# tulip_breakout.net
KiCad netlist of a schematic drawn in EAGLE
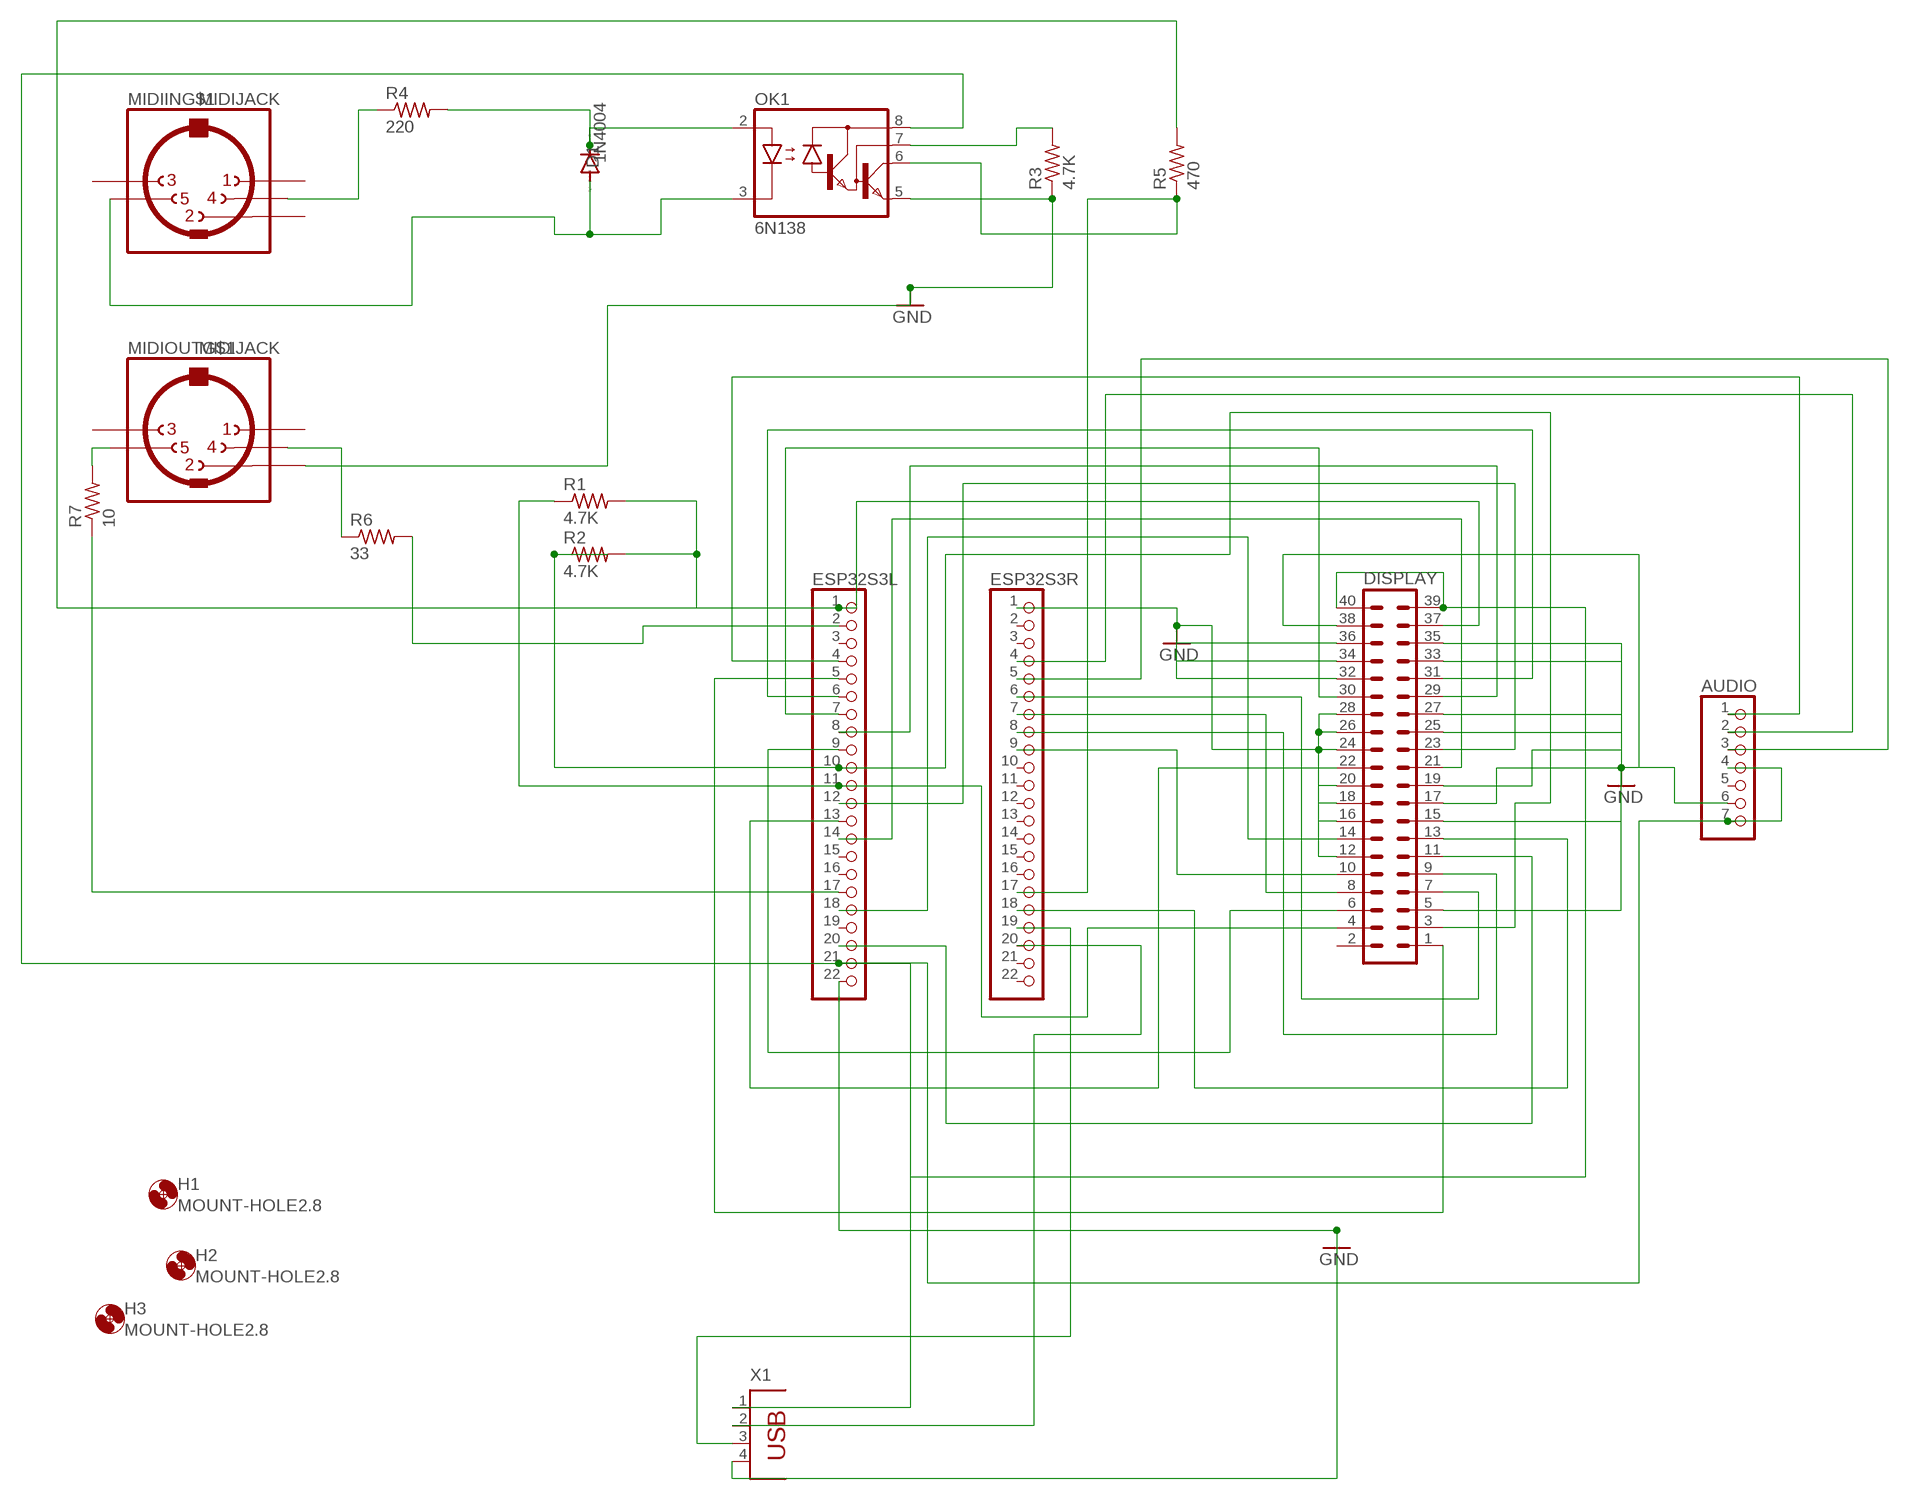
[diagram p0: schematic, sheet 1]

(export (version "E")
  (design (tool "Eeschema 10.0.6"))
  (components
    (comp (ref "AUDIO")
      (value "PINHD-1X7")
      (footprint "eagle-import:1X07")
      (libsource (lib "eagle-import") (part "PINHD-1X7"))
    )
    (comp (ref "D1")
      (value "1N4004")
      (footprint "eagle-import:DO41-10")
      (libsource (lib "eagle-import") (part "1N4004"))
    )
    (comp (ref "DISPLAY")
      (value "MA20-2")
      (footprint "eagle-import:MA20-2")
      (libsource (lib "eagle-import") (part "MA20-2"))
    )
    (comp (ref "ESP32S3L")
      (value "PINHD-1X22")
      (footprint "eagle-import:1X22")
      (libsource (lib "eagle-import") (part "PINHD-1X22"))
    )
    (comp (ref "ESP32S3R")
      (value "PINHD-1X22")
      (footprint "eagle-import:1X22")
      (libsource (lib "eagle-import") (part "PINHD-1X22"))
    )
    (comp (ref "H1")
      (value "MOUNT-HOLE2.8")
      (footprint "eagle-import:2,8")
      (libsource (lib "eagle-import") (part "MOUNT-HOLE2.8"))
    )
    (comp (ref "H2")
      (value "MOUNT-HOLE2.8")
      (footprint "eagle-import:2,8")
      (libsource (lib "eagle-import") (part "MOUNT-HOLE2.8"))
    )
    (comp (ref "H3")
      (value "MOUNT-HOLE2.8")
      (footprint "eagle-import:2,8")
      (libsource (lib "eagle-import") (part "MOUNT-HOLE2.8"))
    )
    (comp (ref "MIDIIN")
      (value "MIDIJACK")
      (footprint "eagle-import:CP-2350")
      (libsource (lib "eagle-import") (part "MIDIJACK"))
    )
    (comp (ref "MIDIOUT")
      (value "MIDIJACK")
      (footprint "eagle-import:CP-2350")
      (libsource (lib "eagle-import") (part "MIDIJACK"))
    )
    (comp (ref "OK1")
      (value "6N138")
      (footprint "eagle-import:DIL08")
      (fields (field (name "MF") "VISHAY/TELEFUNKEN"))
      (libsource (lib "eagle-import") (part "6N138"))
    )
    (comp (ref "R1")
      (value "4.7K")
      (footprint "eagle-import:0204_7")
      (libsource (lib "eagle-import") (part "R-US_0204/7"))
    )
    (comp (ref "R2")
      (value "4.7K")
      (footprint "eagle-import:0204_7")
      (libsource (lib "eagle-import") (part "R-US_0204/7"))
    )
    (comp (ref "R3")
      (value "4.7K")
      (footprint "eagle-import:0204_7")
      (libsource (lib "eagle-import") (part "R-US_0204/7"))
    )
    (comp (ref "R4")
      (value "220")
      (footprint "eagle-import:0204_7")
      (libsource (lib "eagle-import") (part "R-US_0204/7"))
    )
    (comp (ref "R5")
      (value "470")
      (footprint "eagle-import:0204_7")
      (libsource (lib "eagle-import") (part "R-US_0204/7"))
    )
    (comp (ref "R6")
      (value "33")
      (footprint "eagle-import:0204_7")
      (libsource (lib "eagle-import") (part "R-US_0204/7"))
    )
    (comp (ref "R7")
      (value "10")
      (footprint "eagle-import:0204_7")
      (libsource (lib "eagle-import") (part "R-US_0204/7"))
    )
    (comp (ref "X1")
      (value "PN87520")
      (footprint "eagle-import:PN87520")
      (libsource (lib "eagle-import") (part "PN87520"))
    )
  )
  (nets
    (net (code "1") (name "GND") (class "Default")
      (node (ref "AUDIO") (pin "6") (pinfunction "6_6") (pintype "passive"))
      (node (ref "DISPLAY") (pin "12") (pinfunction "12_12") (pintype "passive"))
      (node (ref "DISPLAY") (pin "15") (pinfunction "15_15") (pintype "passive"))
      (node (ref "DISPLAY") (pin "16") (pinfunction "16_16") (pintype "passive"))
      (node (ref "DISPLAY") (pin "17") (pinfunction "17_17") (pintype "passive"))
      (node (ref "DISPLAY") (pin "18") (pinfunction "18_18") (pintype "passive"))
      (node (ref "DISPLAY") (pin "19") (pinfunction "19_19") (pintype "passive"))
      (node (ref "DISPLAY") (pin "20") (pinfunction "20_20") (pintype "passive"))
      (node (ref "DISPLAY") (pin "24") (pinfunction "24_24") (pintype "passive"))
      (node (ref "DISPLAY") (pin "25") (pinfunction "25_25") (pintype "passive"))
      (node (ref "DISPLAY") (pin "26") (pinfunction "26_26") (pintype "passive"))
      (node (ref "DISPLAY") (pin "27") (pinfunction "27_27") (pintype "passive"))
      (node (ref "DISPLAY") (pin "28") (pinfunction "28_28") (pintype "passive"))
      (node (ref "DISPLAY") (pin "32") (pinfunction "32_32") (pintype "passive"))
      (node (ref "DISPLAY") (pin "33") (pinfunction "33_33") (pintype "passive"))
      (node (ref "DISPLAY") (pin "34") (pinfunction "34_34") (pintype "passive"))
      (node (ref "DISPLAY") (pin "35") (pinfunction "35_35") (pintype "passive"))
      (node (ref "DISPLAY") (pin "36") (pinfunction "36_36") (pintype "passive"))
      (node (ref "DISPLAY") (pin "38") (pinfunction "38_38") (pintype "passive"))
      (node (ref "DISPLAY") (pin "5") (pinfunction "5_5") (pintype "passive"))
      (node (ref "ESP32S3L") (pin "22") (pinfunction "22_22") (pintype "passive"))
      (node (ref "ESP32S3R") (pin "1") (pinfunction "1_1") (pintype "passive"))
      (node (ref "MIDIOUT") (pin "2") (pinfunction "2_2") (pintype "passive"))
      (node (ref "OK1") (pin "5") (pinfunction "GND_5") (pintype "passive"))
      (node (ref "R3") (pin "1") (pinfunction "1_1") (pintype "passive"))
      (node (ref "X1") (pin "4") (pinfunction "4_4") (pintype "passive"))
    )
    (net (code "2") (name "Net-(AUDIO-Pad1)") (class "Default")
      (node (ref "AUDIO") (pin "1") (pinfunction "1_1") (pintype "passive"))
      (node (ref "ESP32S3L") (pin "4") (pinfunction "4_4") (pintype "passive"))
    )
    (net (code "3") (name "Net-(AUDIO-Pad2)") (class "Default")
      (node (ref "AUDIO") (pin "2") (pinfunction "2_2") (pintype "passive"))
      (node (ref "ESP32S3R") (pin "4") (pinfunction "4_4") (pintype "passive"))
    )
    (net (code "4") (name "Net-(AUDIO-Pad3)") (class "Default")
      (node (ref "AUDIO") (pin "3") (pinfunction "3_3") (pintype "passive"))
      (node (ref "ESP32S3R") (pin "5") (pinfunction "5_5") (pintype "passive"))
    )
    (net (code "5") (name "Net-(DISPLAY-Pad1)") (class "Default")
      (node (ref "DISPLAY") (pin "1") (pinfunction "1_1") (pintype "passive"))
      (node (ref "ESP32S3L") (pin "5") (pinfunction "5_5") (pintype "passive"))
    )
    (net (code "6") (name "Net-(DISPLAY-Pad3)") (class "Default")
      (node (ref "DISPLAY") (pin "3") (pinfunction "3_3") (pintype "passive"))
      (node (ref "ESP32S3L") (pin "10") (pinfunction "10_10") (pintype "passive"))
      (node (ref "R2") (pin "1") (pinfunction "1_1") (pintype "passive"))
    )
    (net (code "7") (name "Net-(DISPLAY-Pad4)") (class "Default")
      (node (ref "DISPLAY") (pin "4") (pinfunction "4_4") (pintype "passive"))
      (node (ref "ESP32S3L") (pin "11") (pinfunction "11_11") (pintype "passive"))
      (node (ref "R1") (pin "1") (pinfunction "1_1") (pintype "passive"))
    )
    (net (code "8") (name "Net-(DISPLAY-Pad6)") (class "Default")
      (node (ref "DISPLAY") (pin "6") (pinfunction "6_6") (pintype "passive"))
      (node (ref "ESP32S3L") (pin "9") (pinfunction "9_9") (pintype "passive"))
    )
    (net (code "9") (name "Net-(DISPLAY-Pad7)") (class "Default")
      (node (ref "DISPLAY") (pin "7") (pinfunction "7_7") (pintype "passive"))
      (node (ref "ESP32S3R") (pin "6") (pinfunction "6_6") (pintype "passive"))
    )
    (net (code "10") (name "Net-(DISPLAY-Pad8)") (class "Default")
      (node (ref "DISPLAY") (pin "8") (pinfunction "8_8") (pintype "passive"))
      (node (ref "ESP32S3R") (pin "7") (pinfunction "7_7") (pintype "passive"))
    )
    (net (code "11") (name "Net-(DISPLAY-Pad9)") (class "Default")
      (node (ref "DISPLAY") (pin "9") (pinfunction "9_9") (pintype "passive"))
      (node (ref "ESP32S3R") (pin "8") (pinfunction "8_8") (pintype "passive"))
    )
    (net (code "12") (name "Net-(DISPLAY-Pad10)") (class "Default")
      (node (ref "DISPLAY") (pin "10") (pinfunction "10_10") (pintype "passive"))
      (node (ref "ESP32S3R") (pin "9") (pinfunction "9_9") (pintype "passive"))
    )
    (net (code "13") (name "Net-(DISPLAY-Pad11)") (class "Default")
      (node (ref "DISPLAY") (pin "11") (pinfunction "11_11") (pintype "passive"))
      (node (ref "ESP32S3L") (pin "20") (pinfunction "20_20") (pintype "passive"))
    )
    (net (code "14") (name "Net-(DISPLAY-Pad13)") (class "Default")
      (node (ref "DISPLAY") (pin "13") (pinfunction "13_13") (pintype "passive"))
      (node (ref "ESP32S3R") (pin "18") (pinfunction "18_18") (pintype "passive"))
    )
    (net (code "15") (name "Net-(DISPLAY-Pad14)") (class "Default")
      (node (ref "DISPLAY") (pin "14") (pinfunction "14_14") (pintype "passive"))
      (node (ref "ESP32S3L") (pin "18") (pinfunction "18_18") (pintype "passive"))
    )
    (net (code "16") (name "Net-(DISPLAY-Pad21)") (class "Default")
      (node (ref "DISPLAY") (pin "21") (pinfunction "21_21") (pintype "passive"))
      (node (ref "ESP32S3L") (pin "14") (pinfunction "14_14") (pintype "passive"))
    )
    (net (code "17") (name "Net-(DISPLAY-Pad22)") (class "Default")
      (node (ref "DISPLAY") (pin "22") (pinfunction "22_22") (pintype "passive"))
      (node (ref "ESP32S3L") (pin "13") (pinfunction "13_13") (pintype "passive"))
    )
    (net (code "18") (name "Net-(DISPLAY-Pad23)") (class "Default")
      (node (ref "DISPLAY") (pin "23") (pinfunction "23_23") (pintype "passive"))
      (node (ref "ESP32S3L") (pin "12") (pinfunction "12_12") (pintype "passive"))
    )
    (net (code "19") (name "Net-(DISPLAY-Pad29)") (class "Default")
      (node (ref "DISPLAY") (pin "29") (pinfunction "29_29") (pintype "passive"))
      (node (ref "ESP32S3L") (pin "8") (pinfunction "8_8") (pintype "passive"))
    )
    (net (code "20") (name "Net-(DISPLAY-Pad30)") (class "Default")
      (node (ref "DISPLAY") (pin "30") (pinfunction "30_30") (pintype "passive"))
      (node (ref "ESP32S3L") (pin "7") (pinfunction "7_7") (pintype "passive"))
    )
    (net (code "21") (name "Net-(DISPLAY-Pad31)") (class "Default")
      (node (ref "DISPLAY") (pin "31") (pinfunction "31_31") (pintype "passive"))
      (node (ref "ESP32S3L") (pin "6") (pinfunction "6_6") (pintype "passive"))
    )
    (net (code "22") (name "Net-(DISPLAY-Pad37)") (class "Default")
      (node (ref "DISPLAY") (pin "37") (pinfunction "37_37") (pintype "passive"))
      (node (ref "ESP32S3L") (pin "1") (pinfunction "1_1") (pintype "passive"))
      (node (ref "R1") (pin "2") (pinfunction "2_2") (pintype "passive"))
      (node (ref "R2") (pin "2") (pinfunction "2_2") (pintype "passive"))
      (node (ref "R5") (pin "2") (pinfunction "2_2") (pintype "passive"))
    )
    (net (code "23") (name "Net-(ESP32S3L-Pad2)") (class "Default")
      (node (ref "ESP32S3L") (pin "2") (pinfunction "2_2") (pintype "passive"))
      (node (ref "R6") (pin "2") (pinfunction "2_2") (pintype "passive"))
    )
    (net (code "24") (name "Net-(ESP32S3L-Pad17)") (class "Default")
      (node (ref "ESP32S3L") (pin "17") (pinfunction "17_17") (pintype "passive"))
      (node (ref "R7") (pin "1") (pinfunction "1_1") (pintype "passive"))
    )
    (net (code "25") (name "Net-(ESP32S3R-Pad19)") (class "Default")
      (node (ref "ESP32S3R") (pin "19") (pinfunction "19_19") (pintype "passive"))
      (node (ref "X1") (pin "3") (pinfunction "3_3") (pintype "passive"))
    )
    (net (code "26") (name "Net-(ESP32S3R-Pad20)") (class "Default")
      (node (ref "ESP32S3R") (pin "20") (pinfunction "20_20") (pintype "passive"))
      (node (ref "X1") (pin "2") (pinfunction "2_2") (pintype "passive"))
    )
    (net (code "27") (name "Net-(MIDIIN-Pad4)") (class "Default")
      (node (ref "MIDIIN") (pin "4") (pinfunction "4_4") (pintype "passive"))
      (node (ref "R4") (pin "1") (pinfunction "1_1") (pintype "passive"))
    )
    (net (code "28") (name "Net-(MIDIOUT-Pad4)") (class "Default")
      (node (ref "MIDIOUT") (pin "4") (pinfunction "4_4") (pintype "passive"))
      (node (ref "R6") (pin "1") (pinfunction "1_1") (pintype "passive"))
    )
    (net (code "29") (name "Net-(MIDIOUT-Pad5)") (class "Default")
      (node (ref "MIDIOUT") (pin "5") (pinfunction "5_5") (pintype "passive"))
      (node (ref "R7") (pin "2") (pinfunction "2_2") (pintype "passive"))
    )
    (net (code "30") (name "Net-(OK1-A)") (class "Default")
      (node (ref "D1") (pin "C") (pinfunction "C_C") (pintype "passive"))
      (node (ref "OK1") (pin "2") (pinfunction "A_2") (pintype "passive"))
      (node (ref "R4") (pin "2") (pinfunction "2_2") (pintype "passive"))
    )
    (net (code "31") (name "Net-(OK1-C)") (class "Default")
      (node (ref "D1") (pin "A") (pinfunction "A_A") (pintype "passive"))
      (node (ref "MIDIIN") (pin "5") (pinfunction "5_5") (pintype "passive"))
      (node (ref "OK1") (pin "3") (pinfunction "C_3") (pintype "passive"))
    )
    (net (code "32") (name "Net-(OK1-VB)") (class "Default")
      (node (ref "OK1") (pin "7") (pinfunction "VB_7") (pintype "passive"))
      (node (ref "R3") (pin "2") (pinfunction "2_2") (pintype "passive"))
    )
    (net (code "33") (name "Net-(OK1-VCC)") (class "Default")
      (node (ref "AUDIO") (pin "4") (pinfunction "4_4") (pintype "passive"))
      (node (ref "AUDIO") (pin "7") (pinfunction "7_7") (pintype "passive"))
      (node (ref "DISPLAY") (pin "39") (pinfunction "39_39") (pintype "passive"))
      (node (ref "DISPLAY") (pin "40") (pinfunction "40_40") (pintype "passive"))
      (node (ref "ESP32S3L") (pin "21") (pinfunction "21_21") (pintype "passive"))
      (node (ref "OK1") (pin "8") (pinfunction "VCC_8") (pintype "passive"))
      (node (ref "X1") (pin "1") (pinfunction "1_1") (pintype "passive"))
    )
    (net (code "34") (name "Net-(OK1-VO)") (class "Default")
      (node (ref "ESP32S3R") (pin "17") (pinfunction "17_17") (pintype "passive"))
      (node (ref "OK1") (pin "6") (pinfunction "VO_6") (pintype "passive"))
      (node (ref "R5") (pin "1") (pinfunction "1_1") (pintype "passive"))
    )
    (net (code "35") (name "unconnected-(AUDIO-Pad5)") (class "Default")
      (node (ref "AUDIO") (pin "5") (pinfunction "5_5") (pintype "passive"))
    )
    (net (code "36") (name "unconnected-(DISPLAY-Pad2)") (class "Default")
      (node (ref "DISPLAY") (pin "2") (pinfunction "2_2") (pintype "passive"))
    )
    (net (code "37") (name "unconnected-(ESP32S3L-Pad3)") (class "Default")
      (node (ref "ESP32S3L") (pin "3") (pinfunction "3_3") (pintype "passive"))
    )
    (net (code "38") (name "unconnected-(ESP32S3L-Pad15)") (class "Default")
      (node (ref "ESP32S3L") (pin "15") (pinfunction "15_15") (pintype "passive"))
    )
    (net (code "39") (name "unconnected-(ESP32S3L-Pad16)") (class "Default")
      (node (ref "ESP32S3L") (pin "16") (pinfunction "16_16") (pintype "passive"))
    )
    (net (code "40") (name "unconnected-(ESP32S3L-Pad19)") (class "Default")
      (node (ref "ESP32S3L") (pin "19") (pinfunction "19_19") (pintype "passive"))
    )
    (net (code "41") (name "unconnected-(ESP32S3R-Pad2)") (class "Default")
      (node (ref "ESP32S3R") (pin "2") (pinfunction "2_2") (pintype "passive"))
    )
    (net (code "42") (name "unconnected-(ESP32S3R-Pad3)") (class "Default")
      (node (ref "ESP32S3R") (pin "3") (pinfunction "3_3") (pintype "passive"))
    )
    (net (code "43") (name "unconnected-(ESP32S3R-Pad10)") (class "Default")
      (node (ref "ESP32S3R") (pin "10") (pinfunction "10_10") (pintype "passive"))
    )
    (net (code "44") (name "unconnected-(ESP32S3R-Pad11)") (class "Default")
      (node (ref "ESP32S3R") (pin "11") (pinfunction "11_11") (pintype "passive"))
    )
    (net (code "45") (name "unconnected-(ESP32S3R-Pad12)") (class "Default")
      (node (ref "ESP32S3R") (pin "12") (pinfunction "12_12") (pintype "passive"))
    )
    (net (code "46") (name "unconnected-(ESP32S3R-Pad13)") (class "Default")
      (node (ref "ESP32S3R") (pin "13") (pinfunction "13_13") (pintype "passive"))
    )
    (net (code "47") (name "unconnected-(ESP32S3R-Pad14)") (class "Default")
      (node (ref "ESP32S3R") (pin "14") (pinfunction "14_14") (pintype "passive"))
    )
    (net (code "48") (name "unconnected-(ESP32S3R-Pad15)") (class "Default")
      (node (ref "ESP32S3R") (pin "15") (pinfunction "15_15") (pintype "passive"))
    )
    (net (code "49") (name "unconnected-(ESP32S3R-Pad16)") (class "Default")
      (node (ref "ESP32S3R") (pin "16") (pinfunction "16_16") (pintype "passive"))
    )
    (net (code "50") (name "unconnected-(ESP32S3R-Pad21)") (class "Default")
      (node (ref "ESP32S3R") (pin "21") (pinfunction "21_21") (pintype "passive"))
    )
    (net (code "51") (name "unconnected-(ESP32S3R-Pad22)") (class "Default")
      (node (ref "ESP32S3R") (pin "22") (pinfunction "22_22") (pintype "passive"))
    )
    (net (code "52") (name "unconnected-(MIDIIN-Pad1)") (class "Default")
      (node (ref "MIDIIN") (pin "1") (pinfunction "1_1") (pintype "passive"))
    )
    (net (code "53") (name "unconnected-(MIDIIN-Pad2)") (class "Default")
      (node (ref "MIDIIN") (pin "2") (pinfunction "2_2") (pintype "passive"))
    )
    (net (code "54") (name "unconnected-(MIDIIN-Pad3)") (class "Default")
      (node (ref "MIDIIN") (pin "3") (pinfunction "3_3") (pintype "passive"))
    )
    (net (code "55") (name "unconnected-(MIDIOUT-Pad1)") (class "Default")
      (node (ref "MIDIOUT") (pin "1") (pinfunction "1_1") (pintype "passive"))
    )
    (net (code "56") (name "unconnected-(MIDIOUT-Pad3)") (class "Default")
      (node (ref "MIDIOUT") (pin "3") (pinfunction "3_3") (pintype "passive"))
    )
  )
)
